# G-CU_2023-06-21_21-38-10.net
KiCad netlist of a schematic drawn in EasyEDA Pro
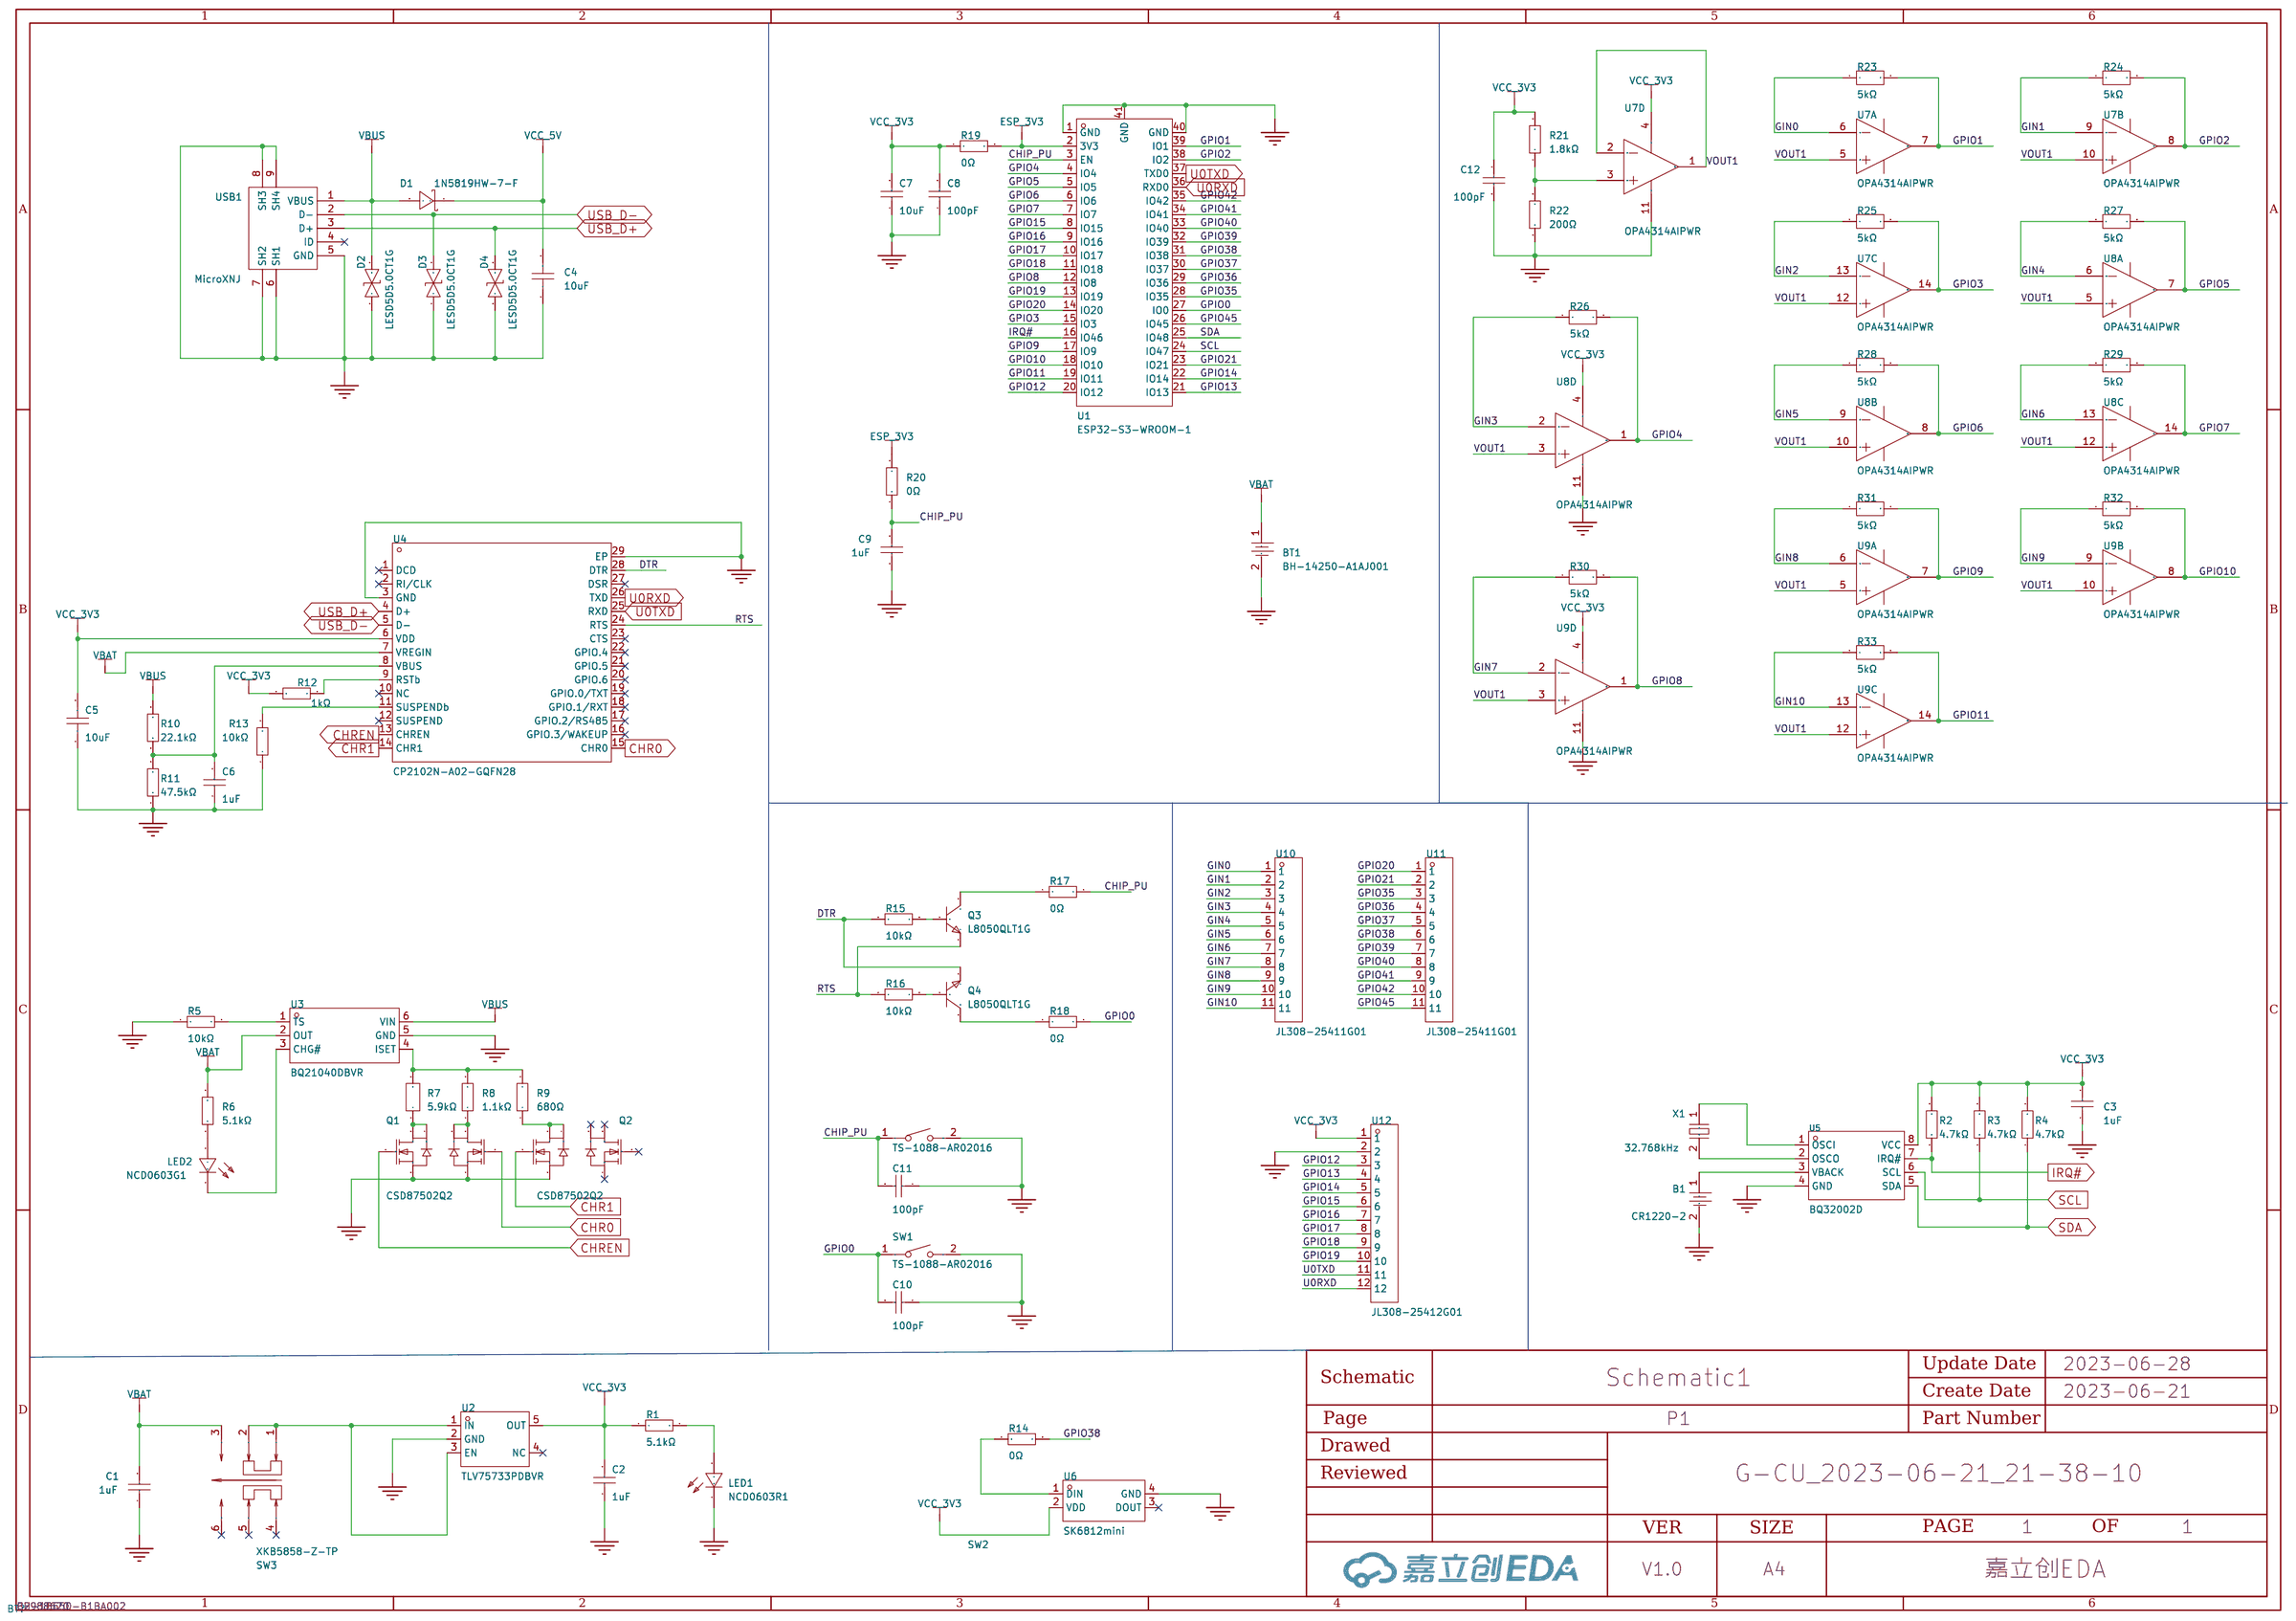
[diagram p0: schematic sheet]

(export (version "E")
  (design (tool "Eeschema 10.0.6"))
  (components
    (comp (ref "B1")
      (value "CR1220-2")
      (footprint "easyedapro:BAT-SMD_CR1220-2")
      (description "连接器类型:电池底座;适用电池规格:CR1220;工作温度范围:-;")
      (fields (field (name "Manufacturer") "Q&J"))
      (libsource (lib "easyedapro") (part "CR1220-2"))
    )
    (comp (ref "BT1")
      (value "BH-14250-A1AJ001")
      (footprint "easyedapro:14250")
      (fields (field (name "Manufacturer") "MYOUNG(美阳)"))
      (libsource (lib "easyedapro") (part "14250"))
    )
    (comp (ref "C1")
      (value "1uF")
      (footprint "easyedapro:C0402")
      (description "容值:1uF;精度:±10%;额定电压:10V;材质(温度系数):X5R;")
      (fields
        (field (name "Manufacturer Part") "CL05A105KP5NNNC")
        (field (name "Manufacturer") "SAMSUNG(三星)")
      )
      (libsource (lib "easyedapro") (part "CL05A105KP5NNNC"))
    )
    (comp (ref "C2")
      (value "1uF")
      (footprint "easyedapro:C0402")
      (description "容值:1uF;精度:±10%;额定电压:10V;材质(温度系数):X5R;")
      (fields
        (field (name "Manufacturer Part") "CL05A105KP5NNNC")
        (field (name "Manufacturer") "SAMSUNG(三星)")
      )
      (libsource (lib "easyedapro") (part "CL05A105KP5NNNC"))
    )
    (comp (ref "C3")
      (value "1uF")
      (footprint "easyedapro:C0402")
      (description "容值:1uF;精度:±10%;额定电压:10V;材质(温度系数):X5R;")
      (fields
        (field (name "Manufacturer Part") "CL05A105KP5NNNC")
        (field (name "Manufacturer") "SAMSUNG(三星)")
      )
      (libsource (lib "easyedapro") (part "CL05A105KP5NNNC"))
    )
    (comp (ref "C4")
      (value "10uF")
      (footprint "easyedapro:C0603")
      (description "容值:10uF;精度:±20%;额定电压:25V;材质(温度系数):X5R;")
      (fields
        (field (name "Manufacturer Part") "CL10A106MA8NRNC")
        (field (name "Manufacturer") "SAMSUNG(三星)")
      )
      (libsource (lib "easyedapro") (part "CL10A106MA8NRNC"))
    )
    (comp (ref "C5")
      (value "10uF")
      (footprint "easyedapro:C0603")
      (description "容值:10uF;精度:±20%;额定电压:25V;材质(温度系数):X5R;")
      (fields
        (field (name "Manufacturer Part") "CL10A106MA8NRNC")
        (field (name "Manufacturer") "SAMSUNG(三星)")
      )
      (libsource (lib "easyedapro") (part "CL10A106MA8NRNC"))
    )
    (comp (ref "C6")
      (value "1uF")
      (footprint "easyedapro:C0603")
      (description "容值:1uF;精度:±10%;额定电压:16V;材质(温度系数):X5R;")
      (fields
        (field (name "Manufacturer Part") "CL10A105KO8NNNC")
        (field (name "Manufacturer") "SAMSUNG(三星)")
      )
      (libsource (lib "easyedapro") (part "CL10A105KO8NNNC"))
    )
    (comp (ref "C7")
      (value "10uF")
      (footprint "easyedapro:C0402")
      (description "容值:10uF;精度:±20%;额定电压:6.3V;材质(温度系数):X5R;")
      (fields
        (field (name "Manufacturer Part") "CL05A106MQ5NUNC")
        (field (name "Manufacturer") "SAMSUNG(三星)")
      )
      (libsource (lib "easyedapro") (part "CL05A106MQ5NUNC"))
    )
    (comp (ref "C8")
      (value "100pF")
      (footprint "easyedapro:C0402")
      (description "容值:100pF;精度:±5%;额定电压:50V;材质(温度系数):C0G;")
      (fields (field (name "Manufacturer Part") "0402CG101J500NT") (field (name "Manufacturer") "FH(风华)"))
      (libsource (lib "easyedapro") (part "0402CG101J500NT"))
    )
    (comp (ref "C9")
      (value "1uF")
      (footprint "easyedapro:C0402")
      (description "容值:1uF;精度:±10%;额定电压:10V;材质(温度系数):X5R;")
      (fields
        (field (name "Manufacturer Part") "CL05A105KP5NNNC")
        (field (name "Manufacturer") "SAMSUNG(三星)")
      )
      (libsource (lib "easyedapro") (part "CL05A105KP5NNNC"))
    )
    (comp (ref "C10")
      (value "100pF")
      (footprint "easyedapro:C0402")
      (description "容值:100pF;精度:±5%;额定电压:50V;材质(温度系数):C0G;")
      (fields (field (name "Manufacturer Part") "0402CG101J500NT") (field (name "Manufacturer") "FH(风华)"))
      (libsource (lib "easyedapro") (part "0402CG101J500NT"))
    )
    (comp (ref "C11")
      (value "100pF")
      (footprint "easyedapro:C0402")
      (description "容值:100pF;精度:±5%;额定电压:50V;材质(温度系数):C0G;")
      (fields (field (name "Manufacturer Part") "0402CG101J500NT") (field (name "Manufacturer") "FH(风华)"))
      (libsource (lib "easyedapro") (part "0402CG101J500NT"))
    )
    (comp (ref "C12")
      (value "100pF")
      (footprint "easyedapro:C0402")
      (description "容值:100pF;精度:±5%;额定电压:50V;材质(温度系数):C0G;")
      (fields (field (name "Manufacturer Part") "0402CG101J500NT") (field (name "Manufacturer") "FH(风华)"))
      (libsource (lib "easyedapro") (part "0402CG101J500NT"))
    )
    (comp (ref "D1")
      (value "1N5819HW-7-F")
      (footprint "easyedapro:SOD-123_L2.7-W1.6-LS3.7-RD")
      (description "直流反向耐压(Vr):40V;平均整流电流(Io):1A;正向压降(Vf):450mV@1A;")
      (fields (field (name "Manufacturer") "DIODES(美台)"))
      (libsource (lib "easyedapro") (part "1N5819HW-7-F"))
    )
    (comp (ref "D2")
      (value "LESD5D5.0CT1G")
      (footprint "easyedapro:SOD-523_L1.2-W0.8-LS1.6-BI")
      (description "极性:双向;反向截止电压(Vrwm):5V;击穿电压(VBR):5.6V;钳位电压(Vc)@Ipp:18.6V;")
      (fields (field (name "Manufacturer") "LRC(乐山无线电)"))
      (libsource (lib "easyedapro") (part "LESD5D5.0CT1G"))
    )
    (comp (ref "D3")
      (value "LESD5D5.0CT1G")
      (footprint "easyedapro:SOD-523_L1.2-W0.8-LS1.6-BI")
      (description "极性:双向;反向截止电压(Vrwm):5V;击穿电压(VBR):5.6V;钳位电压(Vc)@Ipp:18.6V;")
      (fields (field (name "Manufacturer") "LRC(乐山无线电)"))
      (libsource (lib "easyedapro") (part "LESD5D5.0CT1G"))
    )
    (comp (ref "D4")
      (value "LESD5D5.0CT1G")
      (footprint "easyedapro:SOD-523_L1.2-W0.8-LS1.6-BI")
      (description "极性:双向;反向截止电压(Vrwm):5V;击穿电压(VBR):5.6V;钳位电压(Vc)@Ipp:18.6V;")
      (fields (field (name "Manufacturer") "LRC(乐山无线电)"))
      (libsource (lib "easyedapro") (part "LESD5D5.0CT1G"))
    )
    (comp (ref "LED1")
      (value "NCD0603R1")
      (footprint "easyedapro:LED0603-RD_RED")
      (description "发光颜色:红灯;")
      (fields (field (name "Manufacturer") "国星光电"))
      (libsource (lib "easyedapro") (part "FC-DA1608HRK-620D"))
    )
    (comp (ref "LED2")
      (value "NCD0603G1")
      (footprint "easyedapro:LED0603-RD")
      (description "发光颜色:翠绿;")
      (fields (field (name "Manufacturer") "国星光电"))
      (libsource (lib "easyedapro") (part "FC-D1608UGK-520D10"))
    )
    (comp (ref "Q1")
      (value "CSD87502Q2")
      (footprint "easyedapro:DFN-6L_L2.0-W2.0-P0.65-BL-EP")
      (description "类型:2个N沟道;漏源电压(Vdss):30V;连续漏极电流(Id):5A;功率(Pd):2.3W;导通电阻(RDS(on)@Vgs,Id):32.4mΩ@10V,4A;")
      (fields (field (name "Manufacturer") "TI(德州仪器)"))
      (libsource (lib "easyedapro") (part "CSD87502Q2"))
    )
    (comp (ref "Q2")
      (value "CSD87502Q2")
      (footprint "easyedapro:DFN-6L_L2.0-W2.0-P0.65-BL-EP")
      (description "类型:2个N沟道;漏源电压(Vdss):30V;连续漏极电流(Id):5A;功率(Pd):2.3W;导通电阻(RDS(on)@Vgs,Id):32.4mΩ@10V,4A;")
      (fields (field (name "Manufacturer") "TI(德州仪器)"))
      (libsource (lib "easyedapro") (part "CSD87502Q2"))
    )
    (comp (ref "Q3")
      (value "L8050QLT1G")
      (footprint "easyedapro:SOT-23-3_L2.9-W1.3-P1.90-LS2.4-BR")
      (description "晶体管类型:NPN;集射极击穿电压(Vceo):25V;集电极电流(Ic):800mA;功率(Pd):225mW;")
      (fields (field (name "Manufacturer") "LRC(乐山无线电)"))
      (libsource (lib "easyedapro") (part "L8050QLT1G"))
    )
    (comp (ref "Q4")
      (value "L8050QLT1G")
      (footprint "easyedapro:SOT-23-3_L2.9-W1.3-P1.90-LS2.4-BR")
      (description "晶体管类型:NPN;集射极击穿电压(Vceo):25V;集电极电流(Ic):800mA;功率(Pd):225mW;")
      (fields (field (name "Manufacturer") "LRC(乐山无线电)"))
      (libsource (lib "easyedapro") (part "L8050QLT1G"))
    )
    (comp (ref "R1")
      (value "5.1kΩ")
      (footprint "easyedapro:R0402")
      (description "电阻类型:厚膜电阻;阻值:5.1kΩ;精度:±1%;功率:62.5mW;")
      (fields
        (field (name "Manufacturer Part") "0402WGF5101TCE")
        (field (name "Manufacturer") "UNI-ROYAL(厚声)")
      )
      (libsource (lib "easyedapro") (part "0402WGF5101TCE"))
    )
    (comp (ref "R2")
      (value "4.7kΩ")
      (footprint "easyedapro:R0402")
      (description "电阻类型:厚膜电阻;阻值:4.7kΩ;精度:±1%;功率:62.5mW;")
      (fields
        (field (name "Manufacturer Part") "0402WGF4701TCE")
        (field (name "Manufacturer") "UNI-ROYAL(厚声)")
      )
      (libsource (lib "easyedapro") (part "0402WGF4701TCE"))
    )
    (comp (ref "R3")
      (value "4.7kΩ")
      (footprint "easyedapro:R0402")
      (description "电阻类型:厚膜电阻;阻值:4.7kΩ;精度:±1%;功率:62.5mW;")
      (fields
        (field (name "Manufacturer Part") "0402WGF4701TCE")
        (field (name "Manufacturer") "UNI-ROYAL(厚声)")
      )
      (libsource (lib "easyedapro") (part "0402WGF4701TCE"))
    )
    (comp (ref "R4")
      (value "4.7kΩ")
      (footprint "easyedapro:R0402")
      (description "电阻类型:厚膜电阻;阻值:4.7kΩ;精度:±1%;功率:62.5mW;")
      (fields
        (field (name "Manufacturer Part") "0402WGF4701TCE")
        (field (name "Manufacturer") "UNI-ROYAL(厚声)")
      )
      (libsource (lib "easyedapro") (part "0402WGF4701TCE"))
    )
    (comp (ref "R5")
      (value "10kΩ")
      (footprint "easyedapro:R0402")
      (description "电阻类型:厚膜电阻;阻值:10kΩ;精度:±1%;功率:62.5mW;")
      (fields
        (field (name "Manufacturer Part") "0402WGF1002TCE")
        (field (name "Manufacturer") "UNI-ROYAL(厚声)")
      )
      (libsource (lib "easyedapro") (part "0402WGF1002TCE"))
    )
    (comp (ref "R6")
      (value "5.1kΩ")
      (footprint "easyedapro:R0402")
      (description "电阻类型:厚膜电阻;阻值:5.1kΩ;精度:±1%;功率:62.5mW;")
      (fields
        (field (name "Manufacturer Part") "0402WGF5101TCE")
        (field (name "Manufacturer") "UNI-ROYAL(厚声)")
      )
      (libsource (lib "easyedapro") (part "0402WGF5101TCE"))
    )
    (comp (ref "R7")
      (value "5.9kΩ")
      (footprint "easyedapro:R0402")
      (description "电阻类型:厚膜电阻;阻值:5.9kΩ;精度:±1%;功率:62.5mW;温度系数:±100ppm/°C;最大工作电压:50V;工作温度范围:-55°C~+125°C;")
      (fields (field (name "Manufacturer Part") "RC0402FR-075K9L") (field (name "Manufacturer") "YAGEO(国巨)"))
      (libsource (lib "easyedapro") (part "RC0402FR-075K9L"))
    )
    (comp (ref "R8")
      (value "1.1kΩ")
      (footprint "easyedapro:R0402")
      (description "电阻类型:厚膜电阻;阻值:1.1kΩ;精度:±1%;功率:62.5mW;")
      (fields
        (field (name "Manufacturer Part") "0402WGF1101TCE")
        (field (name "Manufacturer") "UNI-ROYAL(厚声)")
      )
      (libsource (lib "easyedapro") (part "0402WGF1101TCE"))
    )
    (comp (ref "R9")
      (value "680Ω")
      (footprint "easyedapro:R0402")
      (description "电阻类型:厚膜电阻;阻值:680Ω;精度:±1%;功率:62.5mW;")
      (fields
        (field (name "Manufacturer Part") "0402WGF6800TCE")
        (field (name "Manufacturer") "UNI-ROYAL(厚声)")
      )
      (libsource (lib "easyedapro") (part "0402WGF6800TCE"))
    )
    (comp (ref "R10")
      (value "22.1kΩ")
      (footprint "easyedapro:R0402")
      (description "电阻类型:厚膜电阻;阻值:22.1kΩ;精度:±1%;功率:62.5mW;")
      (fields
        (field (name "Manufacturer Part") "0402WGF2212TCE")
        (field (name "Manufacturer") "UNI-ROYAL(厚声)")
      )
      (libsource (lib "easyedapro") (part "0402WGF2212TCE"))
    )
    (comp (ref "R11")
      (value "47.5kΩ")
      (footprint "easyedapro:R0402")
      (description "电阻类型:厚膜电阻;阻值:47.5kΩ;精度:±1%;功率:62.5mW;")
      (fields
        (field (name "Manufacturer Part") "0402WGF4752TCE")
        (field (name "Manufacturer") "UNI-ROYAL(厚声)")
      )
      (libsource (lib "easyedapro") (part "0402WGF4752TCE"))
    )
    (comp (ref "R12")
      (value "1kΩ")
      (footprint "easyedapro:R0402")
      (description "电阻类型:厚膜电阻;阻值:1kΩ;精度:±1%;功率:62.5mW;")
      (fields
        (field (name "Manufacturer Part") "0402WGF1001TCE")
        (field (name "Manufacturer") "UNI-ROYAL(厚声)")
      )
      (libsource (lib "easyedapro") (part "0402WGF1001TCE"))
    )
    (comp (ref "R13")
      (value "10kΩ")
      (footprint "easyedapro:R0402")
      (description "电阻类型:厚膜电阻;阻值:10kΩ;精度:±1%;功率:62.5mW;")
      (fields
        (field (name "Manufacturer Part") "0402WGF1002TCE")
        (field (name "Manufacturer") "UNI-ROYAL(厚声)")
      )
      (libsource (lib "easyedapro") (part "0402WGF1002TCE"))
    )
    (comp (ref "R14")
      (value "0Ω")
      (footprint "easyedapro:R0402")
      (description "电阻类型:厚膜电阻;阻值:0Ω;精度:±5%;功率:62.5mW;")
      (fields
        (field (name "Manufacturer Part") "0402WGJ0000TCE")
        (field (name "Manufacturer") "UNI-ROYAL(厚声)")
      )
      (libsource (lib "easyedapro") (part "0402WGJ0000TCE"))
    )
    (comp (ref "R15")
      (value "10kΩ")
      (footprint "easyedapro:R0402")
      (description "电阻类型:厚膜电阻;阻值:10kΩ;精度:±1%;功率:62.5mW;")
      (fields
        (field (name "Manufacturer Part") "0402WGF1002TCE")
        (field (name "Manufacturer") "UNI-ROYAL(厚声)")
      )
      (libsource (lib "easyedapro") (part "0402WGF1002TCE"))
    )
    (comp (ref "R16")
      (value "10kΩ")
      (footprint "easyedapro:R0402")
      (description "电阻类型:厚膜电阻;阻值:10kΩ;精度:±1%;功率:62.5mW;")
      (fields
        (field (name "Manufacturer Part") "0402WGF1002TCE")
        (field (name "Manufacturer") "UNI-ROYAL(厚声)")
      )
      (libsource (lib "easyedapro") (part "0402WGF1002TCE"))
    )
    (comp (ref "R17")
      (value "0Ω")
      (footprint "easyedapro:R0402")
      (description "电阻类型:厚膜电阻;阻值:0Ω;精度:±5%;功率:62.5mW;")
      (fields
        (field (name "Manufacturer Part") "0402WGJ0000TCE")
        (field (name "Manufacturer") "UNI-ROYAL(厚声)")
      )
      (libsource (lib "easyedapro") (part "0402WGJ0000TCE"))
    )
    (comp (ref "R18")
      (value "0Ω")
      (footprint "easyedapro:R0402")
      (description "电阻类型:厚膜电阻;阻值:0Ω;精度:±5%;功率:62.5mW;")
      (fields
        (field (name "Manufacturer Part") "0402WGJ0000TCE")
        (field (name "Manufacturer") "UNI-ROYAL(厚声)")
      )
      (libsource (lib "easyedapro") (part "0402WGJ0000TCE"))
    )
    (comp (ref "R19")
      (value "0Ω")
      (footprint "easyedapro:R0402")
      (description "电阻类型:厚膜电阻;阻值:0Ω;精度:±5%;功率:62.5mW;")
      (fields
        (field (name "Manufacturer Part") "0402WGJ0000TCE")
        (field (name "Manufacturer") "UNI-ROYAL(厚声)")
      )
      (libsource (lib "easyedapro") (part "0402WGJ0000TCE"))
    )
    (comp (ref "R20")
      (value "0Ω")
      (footprint "easyedapro:R0402")
      (description "电阻类型:厚膜电阻;阻值:0Ω;精度:±5%;功率:62.5mW;")
      (fields
        (field (name "Manufacturer Part") "0402WGJ0000TCE")
        (field (name "Manufacturer") "UNI-ROYAL(厚声)")
      )
      (libsource (lib "easyedapro") (part "0402WGJ0000TCE"))
    )
    (comp (ref "R21")
      (value "1.8kΩ")
      (footprint "easyedapro:R0402")
      (description "电阻类型:厚膜电阻;阻值:1.8kΩ;精度:±1%;功率:62.5mW;")
      (fields
        (field (name "Manufacturer Part") "0402WGF1801TCE")
        (field (name "Manufacturer") "UNI-ROYAL(厚声)")
      )
      (libsource (lib "easyedapro") (part "0402WGF1801TCE"))
    )
    (comp (ref "R22")
      (value "200Ω")
      (footprint "easyedapro:R0402")
      (description "电阻类型:厚膜电阻;阻值:200Ω;精度:±1%;功率:62.5mW;")
      (fields
        (field (name "Manufacturer Part") "0402WGF2000TCE")
        (field (name "Manufacturer") "UNI-ROYAL(厚声)")
      )
      (libsource (lib "easyedapro") (part "0402WGF2000TCE"))
    )
    (comp (ref "R23")
      (value "5kΩ")
      (footprint "easyedapro:R0603")
      (description "电阻类型:薄膜电阻;阻值:5kΩ;精度:±0.1%;功率:100mW;")
      (fields (field (name "Manufacturer Part") "AR03BTCX5001") (field (name "Manufacturer") "Viking(光颉)"))
      (libsource (lib "easyedapro") (part "AR03BTCX5001"))
    )
    (comp (ref "R24")
      (value "5kΩ")
      (footprint "easyedapro:R0603")
      (description "电阻类型:薄膜电阻;阻值:5kΩ;精度:±0.1%;功率:100mW;")
      (fields (field (name "Manufacturer Part") "AR03BTCX5001") (field (name "Manufacturer") "Viking(光颉)"))
      (libsource (lib "easyedapro") (part "AR03BTCX5001"))
    )
    (comp (ref "R25")
      (value "5kΩ")
      (footprint "easyedapro:R0603")
      (description "电阻类型:薄膜电阻;阻值:5kΩ;精度:±0.1%;功率:100mW;")
      (fields (field (name "Manufacturer Part") "AR03BTCX5001") (field (name "Manufacturer") "Viking(光颉)"))
      (libsource (lib "easyedapro") (part "AR03BTCX5001"))
    )
    (comp (ref "R26")
      (value "5kΩ")
      (footprint "easyedapro:R0603")
      (description "电阻类型:薄膜电阻;阻值:5kΩ;精度:±0.1%;功率:100mW;")
      (fields (field (name "Manufacturer Part") "AR03BTCX5001") (field (name "Manufacturer") "Viking(光颉)"))
      (libsource (lib "easyedapro") (part "AR03BTCX5001"))
    )
    (comp (ref "R27")
      (value "5kΩ")
      (footprint "easyedapro:R0603")
      (description "电阻类型:薄膜电阻;阻值:5kΩ;精度:±0.1%;功率:100mW;")
      (fields (field (name "Manufacturer Part") "AR03BTCX5001") (field (name "Manufacturer") "Viking(光颉)"))
      (libsource (lib "easyedapro") (part "AR03BTCX5001"))
    )
    (comp (ref "R28")
      (value "5kΩ")
      (footprint "easyedapro:R0603")
      (description "电阻类型:薄膜电阻;阻值:5kΩ;精度:±0.1%;功率:100mW;")
      (fields (field (name "Manufacturer Part") "AR03BTCX5001") (field (name "Manufacturer") "Viking(光颉)"))
      (libsource (lib "easyedapro") (part "AR03BTCX5001"))
    )
    (comp (ref "R29")
      (value "5kΩ")
      (footprint "easyedapro:R0603")
      (description "电阻类型:薄膜电阻;阻值:5kΩ;精度:±0.1%;功率:100mW;")
      (fields (field (name "Manufacturer Part") "AR03BTCX5001") (field (name "Manufacturer") "Viking(光颉)"))
      (libsource (lib "easyedapro") (part "AR03BTCX5001"))
    )
    (comp (ref "R30")
      (value "5kΩ")
      (footprint "easyedapro:R0603")
      (description "电阻类型:薄膜电阻;阻值:5kΩ;精度:±0.1%;功率:100mW;")
      (fields (field (name "Manufacturer Part") "AR03BTCX5001") (field (name "Manufacturer") "Viking(光颉)"))
      (libsource (lib "easyedapro") (part "AR03BTCX5001"))
    )
    (comp (ref "R31")
      (value "5kΩ")
      (footprint "easyedapro:R0603")
      (description "电阻类型:薄膜电阻;阻值:5kΩ;精度:±0.1%;功率:100mW;")
      (fields (field (name "Manufacturer Part") "AR03BTCX5001") (field (name "Manufacturer") "Viking(光颉)"))
      (libsource (lib "easyedapro") (part "AR03BTCX5001"))
    )
    (comp (ref "R32")
      (value "5kΩ")
      (footprint "easyedapro:R0603")
      (description "电阻类型:薄膜电阻;阻值:5kΩ;精度:±0.1%;功率:100mW;")
      (fields (field (name "Manufacturer Part") "AR03BTCX5001") (field (name "Manufacturer") "Viking(光颉)"))
      (libsource (lib "easyedapro") (part "AR03BTCX5001"))
    )
    (comp (ref "R33")
      (value "5kΩ")
      (footprint "easyedapro:R0603")
      (description "电阻类型:薄膜电阻;阻值:5kΩ;精度:±0.1%;功率:100mW;")
      (fields (field (name "Manufacturer Part") "AR03BTCX5001") (field (name "Manufacturer") "Viking(光颉)"))
      (libsource (lib "easyedapro") (part "AR03BTCX5001"))
    )
    (comp (ref "SW1")
      (value "TS-1088-AR02016")
      (footprint "easyedapro:SW-SMD_L3.9-W3.0-P4.45")
      (description "触点电流:50mA;额定电压(DC):12V;绝缘电阻:100MΩ;电路结构:单刀单掷;安装方式:立贴;作用力:160gf@±50gf;机械寿命:10万次;带支架:否;")
      (fields (field (name "Manufacturer") "XUNPU(讯普)"))
      (libsource (lib "easyedapro") (part "TS-1088-AR02016"))
    )
    (comp (ref "SW2")
      (value "TS-1088-AR02016")
      (footprint "easyedapro:SW-SMD_L3.9-W3.0-P4.45")
      (description "触点电流:50mA;额定电压(DC):12V;绝缘电阻:100MΩ;电路结构:单刀单掷;安装方式:立贴;作用力:160gf@±50gf;机械寿命:10万次;带支架:否;")
      (fields (field (name "Manufacturer") "XUNPU(讯普)"))
      (libsource (lib "easyedapro") (part "TS-1088-AR02016"))
    )
    (comp (ref "SW3")
      (value "XKB5858-Z-TP")
      (footprint "easyedapro:SW-SMD_6P-L5.8-W5.8-P2.00-LS8.5-1")
      (fields (field (name "Manufacturer") "XKB Connectivity(中国星坤)"))
      (libsource (lib "easyedapro") (part "XKB5858-Z-TP_C840833"))
    )
    (comp (ref "U1")
      (value "ESP32-S3-WROOM-1")
      (footprint "easyedapro:WIRELM-SMD_ESP32-S3-WROOM-1")
      (fields (field (name "Manufacturer") "ESPRESSIF(乐鑫)"))
      (libsource (lib "easyedapro") (part "ESP32-S3-WROOM-1"))
    )
    (comp (ref "U2")
      (value "TLV75733PDBVR")
      (footprint "easyedapro:SOT-23-5_L2.9-W1.6-P0.95-LS2.8-BL")
      (description "输出类型:固定;输出极性:正;输出通道数:1;最大输入电压:5.5V;输出电压:3.3V;压差:475mV@(1A);输出电流:1A;电源纹波抑制比(PSRR):52dB;")
      (fields (field (name "Manufacturer") "TI(德州仪器)"))
      (libsource (lib "easyedapro") (part "TLV75733PDBVR"))
    )
    (comp (ref "U3")
      (value "BQ21040DBVR")
      (footprint "easyedapro:SOT-23-6_L2.9-W1.6-P0.95-LS2.8-BR")
      (description "电池类型:锂离子/聚合物;电池节数:1;最大充电电流:800mA;电源电压:6.45V;")
      (fields (field (name "Manufacturer") "TI(德州仪器)"))
      (libsource (lib "easyedapro") (part "BQ21040DBVR"))
    )
    (comp (ref "U4")
      (value "CP2102N-A02-GQFN28")
      (footprint "easyedapro:QFN-28_L5.0-W5.0-P0.50-TL-EP3.3")
      (fields (field (name "Manufacturer") "SILICON LABS(芯科)"))
      (libsource (lib "easyedapro") (part "CP2102N-A02-GQFN28"))
    )
    (comp (ref "U5")
      (value "BQ32002D")
      (footprint "easyedapro:SOIC-8_L4.9-W3.9-P1.27-LS6.0-BL")
      (description "实时时钟 (RTC) 8-SOIC -40 to 85")
      (fields (field (name "Manufacturer") "TI(德州仪器)"))
      (libsource (lib "easyedapro") (part "BQ32002D"))
    )
    (comp (ref "U6")
      (value "SK6812mini")
      (footprint "easyedapro:LED-SMD_4P-L3.7-W3.5-P1.75-BR-SK6812MINI")
      (fields (field (name "Manufacturer") "欧思科光电"))
      (libsource (lib "easyedapro") (part "SK6812MINI"))
    )
    (comp (ref "U7")
      (value "OPA4314AIPWR")
      (footprint "easyedapro:TSSOP-14_L5.0-W4.4-P0.65-LS6.4-BL")
      (description "OPA4314 四路、3MHz、低功耗、低噪声、RRI/O、1.8V CMOS 运算放大器")
      (fields (field (name "Manufacturer") "TI(德州仪器)"))
      (libsource (lib "easyedapro") (part "OPA4314AIPWR"))
    )
    (comp (ref "U8")
      (value "OPA4314AIPWR")
      (footprint "easyedapro:TSSOP-14_L5.0-W4.4-P0.65-LS6.4-BL")
      (description "OPA4314 四路、3MHz、低功耗、低噪声、RRI/O、1.8V CMOS 运算放大器")
      (fields (field (name "Manufacturer") "TI(德州仪器)"))
      (libsource (lib "easyedapro") (part "OPA4314AIPWR"))
    )
    (comp (ref "U9")
      (value "OPA4314AIPWR")
      (footprint "easyedapro:TSSOP-14_L5.0-W4.4-P0.65-LS6.4-BL")
      (description "OPA4314 四路、3MHz、低功耗、低噪声、RRI/O、1.8V CMOS 运算放大器")
      (fields (field (name "Manufacturer") "TI(德州仪器)"))
      (libsource (lib "easyedapro") (part "OPA4314AIPWR"))
    )
    (comp (ref "U10")
      (value "JL308-25411G01")
      (footprint "easyedapro:CONN-TH_11P-P2.54_JILN_JL308-25411G01")
      (fields (field (name "Manufacturer") "JILN(锦凌)"))
      (libsource (lib "easyedapro") (part "JL308-25411G01"))
    )
    (comp (ref "U11")
      (value "JL308-25411G01")
      (footprint "easyedapro:CONN-TH_11P-P2.54_JILN_JL308-25411G01")
      (fields (field (name "Manufacturer") "JILN(锦凌)"))
      (libsource (lib "easyedapro") (part "JL308-25411G01"))
    )
    (comp (ref "U12")
      (value "JL308-25412G01")
      (footprint "easyedapro:CONN-TH_12P-P2.54_JILN_JL308-25412G01")
      (fields (field (name "Manufacturer") "JILN(锦凌)"))
      (libsource (lib "easyedapro") (part "JL308-25412G01"))
    )
    (comp (ref "USB1")
      (value "MicroXNJ")
      (footprint "easyedapro:MICRO-USB-SMD_MICROXNJ")
      (description "连接器类型:Micro-B;标准:USB 2.0;公母:母座;触点数量:5;端口数量:1;安装方式:卧贴;额定电流 - 电源:1A;工作温度范围:-20°C~+85°C;")
      (fields (field (name "Manufacturer") "SHOU HAN(首韩)"))
      (libsource (lib "easyedapro") (part "MICROXNJ"))
    )
    (comp (ref "X1")
      (value "32.768kHz")
      (footprint "easyedapro:CRYSTAL-SMD_L3.2-W1.5")
      (description "频率:32.768kHz;频率公差:±10ppm;负载电容:12.5pF;")
      (fields (field (name "Manufacturer Part") "Q13FC13500005") (field (name "Manufacturer") "EPSON(爱普生)"))
      (libsource (lib "easyedapro") (part "Q13FC13500005"))
    )
  )
  (nets
    (net (code "1") (name "/CHIP_PU") (class "Default")
      (node (ref "C11") (pin "2") (pinfunction "2_2") (pintype "input"))
      (node (ref "C9") (pin "2") (pinfunction "2_2") (pintype "input"))
      (node (ref "R17") (pin "2") (pinfunction "2_2") (pintype "input"))
      (node (ref "R20") (pin "1") (pinfunction "1_1") (pintype "input"))
      (node (ref "SW2") (pin "1") (pinfunction "1_1") (pintype "input"))
      (node (ref "U1") (pin "3") (pinfunction "EN_3") (pintype "input"))
    )
    (net (code "2") (name "/DTR") (class "Default")
      (node (ref "Q4") (pin "2") (pinfunction "E_2") (pintype "input"))
      (node (ref "R15") (pin "1") (pinfunction "1_1") (pintype "input"))
      (node (ref "U4") (pin "28") (pinfunction "DTR_28") (pintype "input"))
    )
    (net (code "3") (name "/GIN0") (class "Default")
      (node (ref "R23") (pin "1") (pinfunction "1_1") (pintype "input"))
      (node (ref "U10") (pin "1") (pinfunction "1_1") (pintype "input"))
      (node (ref "U7") (pin "6") (pinfunction "IN_B-_6") (pintype "input"))
    )
    (net (code "4") (name "/GIN1") (class "Default")
      (node (ref "R24") (pin "1") (pinfunction "1_1") (pintype "input"))
      (node (ref "U10") (pin "2") (pinfunction "2_2") (pintype "input"))
      (node (ref "U7") (pin "9") (pinfunction "IN_C-_9") (pintype "input"))
    )
    (net (code "5") (name "/GIN2") (class "Default")
      (node (ref "R25") (pin "1") (pinfunction "1_1") (pintype "input"))
      (node (ref "U10") (pin "3") (pinfunction "3_3") (pintype "input"))
      (node (ref "U7") (pin "13") (pinfunction "IN_D-_13") (pintype "input"))
    )
    (net (code "6") (name "/GIN3") (class "Default")
      (node (ref "R26") (pin "1") (pinfunction "1_1") (pintype "input"))
      (node (ref "U10") (pin "4") (pinfunction "4_4") (pintype "input"))
      (node (ref "U8") (pin "2") (pinfunction "IN_A-_2") (pintype "input"))
    )
    (net (code "7") (name "/GIN4") (class "Default")
      (node (ref "R27") (pin "1") (pinfunction "1_1") (pintype "input"))
      (node (ref "U10") (pin "5") (pinfunction "5_5") (pintype "input"))
      (node (ref "U8") (pin "6") (pinfunction "IN_B-_6") (pintype "input"))
    )
    (net (code "8") (name "/GIN5") (class "Default")
      (node (ref "R28") (pin "1") (pinfunction "1_1") (pintype "input"))
      (node (ref "U10") (pin "6") (pinfunction "6_6") (pintype "input"))
      (node (ref "U8") (pin "9") (pinfunction "IN_C-_9") (pintype "input"))
    )
    (net (code "9") (name "/GIN6") (class "Default")
      (node (ref "R29") (pin "1") (pinfunction "1_1") (pintype "input"))
      (node (ref "U10") (pin "7") (pinfunction "7_7") (pintype "input"))
      (node (ref "U8") (pin "13") (pinfunction "IN_D-_13") (pintype "input"))
    )
    (net (code "10") (name "/GIN7") (class "Default")
      (node (ref "R30") (pin "1") (pinfunction "1_1") (pintype "input"))
      (node (ref "U10") (pin "8") (pinfunction "8_8") (pintype "input"))
      (node (ref "U9") (pin "2") (pinfunction "IN_A-_2") (pintype "input"))
    )
    (net (code "11") (name "/GIN8") (class "Default")
      (node (ref "R31") (pin "1") (pinfunction "1_1") (pintype "input"))
      (node (ref "U10") (pin "9") (pinfunction "9_9") (pintype "input"))
      (node (ref "U9") (pin "6") (pinfunction "IN_B-_6") (pintype "input"))
    )
    (net (code "12") (name "/GIN9") (class "Default")
      (node (ref "R32") (pin "1") (pinfunction "1_1") (pintype "input"))
      (node (ref "U10") (pin "10") (pinfunction "10_10") (pintype "input"))
      (node (ref "U9") (pin "9") (pinfunction "IN_C-_9") (pintype "input"))
    )
    (net (code "13") (name "/GIN10") (class "Default")
      (node (ref "R33") (pin "1") (pinfunction "1_1") (pintype "input"))
      (node (ref "U10") (pin "11") (pinfunction "11_11") (pintype "input"))
      (node (ref "U9") (pin "13") (pinfunction "IN_D-_13") (pintype "input"))
    )
    (net (code "14") (name "/GPIO0") (class "Default")
      (node (ref "C10") (pin "2") (pinfunction "2_2") (pintype "input"))
      (node (ref "R18") (pin "2") (pinfunction "2_2") (pintype "input"))
      (node (ref "SW1") (pin "1") (pinfunction "1_1") (pintype "input"))
      (node (ref "U1") (pin "27") (pinfunction "IO0_27") (pintype "input"))
    )
    (net (code "15") (name "/GPIO1") (class "Default")
      (node (ref "R23") (pin "2") (pinfunction "2_2") (pintype "input"))
      (node (ref "U1") (pin "39") (pinfunction "IO1_39") (pintype "input"))
      (node (ref "U7") (pin "7") (pinfunction "OUT_B_7") (pintype "output"))
    )
    (net (code "16") (name "/GPIO2") (class "Default")
      (node (ref "R24") (pin "2") (pinfunction "2_2") (pintype "input"))
      (node (ref "U1") (pin "38") (pinfunction "IO2_38") (pintype "input"))
      (node (ref "U7") (pin "8") (pinfunction "OUT_C_8") (pintype "output"))
    )
    (net (code "17") (name "/GPIO3") (class "Default")
      (node (ref "R25") (pin "2") (pinfunction "2_2") (pintype "input"))
      (node (ref "U1") (pin "15") (pinfunction "IO3_15") (pintype "input"))
      (node (ref "U7") (pin "14") (pinfunction "OUT_D_14") (pintype "output"))
    )
    (net (code "18") (name "/GPIO4") (class "Default")
      (node (ref "R26") (pin "2") (pinfunction "2_2") (pintype "input"))
      (node (ref "U1") (pin "4") (pinfunction "IO4_4") (pintype "input"))
      (node (ref "U8") (pin "1") (pinfunction "OUT_A_1") (pintype "output"))
    )
    (net (code "19") (name "/GPIO5") (class "Default")
      (node (ref "R27") (pin "2") (pinfunction "2_2") (pintype "input"))
      (node (ref "U1") (pin "5") (pinfunction "IO5_5") (pintype "input"))
      (node (ref "U8") (pin "7") (pinfunction "OUT_B_7") (pintype "output"))
    )
    (net (code "20") (name "/GPIO6") (class "Default")
      (node (ref "R28") (pin "2") (pinfunction "2_2") (pintype "input"))
      (node (ref "U1") (pin "6") (pinfunction "IO6_6") (pintype "input"))
      (node (ref "U8") (pin "8") (pinfunction "OUT_C_8") (pintype "output"))
    )
    (net (code "21") (name "/GPIO7") (class "Default")
      (node (ref "R29") (pin "2") (pinfunction "2_2") (pintype "input"))
      (node (ref "U1") (pin "7") (pinfunction "IO7_7") (pintype "input"))
      (node (ref "U8") (pin "14") (pinfunction "OUT_D_14") (pintype "output"))
    )
    (net (code "22") (name "/GPIO8") (class "Default")
      (node (ref "R30") (pin "2") (pinfunction "2_2") (pintype "input"))
      (node (ref "U1") (pin "12") (pinfunction "IO8_12") (pintype "input"))
      (node (ref "U9") (pin "1") (pinfunction "OUT_A_1") (pintype "output"))
    )
    (net (code "23") (name "/GPIO9") (class "Default")
      (node (ref "R31") (pin "2") (pinfunction "2_2") (pintype "input"))
      (node (ref "U1") (pin "17") (pinfunction "IO9_17") (pintype "input"))
      (node (ref "U9") (pin "7") (pinfunction "OUT_B_7") (pintype "output"))
    )
    (net (code "24") (name "/GPIO10") (class "Default")
      (node (ref "R32") (pin "2") (pinfunction "2_2") (pintype "input"))
      (node (ref "U1") (pin "18") (pinfunction "IO10_18") (pintype "input"))
      (node (ref "U9") (pin "8") (pinfunction "OUT_C_8") (pintype "output"))
    )
    (net (code "25") (name "/GPIO11") (class "Default")
      (node (ref "R33") (pin "2") (pinfunction "2_2") (pintype "input"))
      (node (ref "U1") (pin "19") (pinfunction "IO11_19") (pintype "input"))
      (node (ref "U9") (pin "14") (pinfunction "OUT_D_14") (pintype "output"))
    )
    (net (code "26") (name "/GPIO12") (class "Default")
      (node (ref "U1") (pin "20") (pinfunction "IO12_20") (pintype "input"))
      (node (ref "U12") (pin "3") (pinfunction "3_3") (pintype "input"))
    )
    (net (code "27") (name "/GPIO13") (class "Default")
      (node (ref "U1") (pin "21") (pinfunction "IO13_21") (pintype "input"))
      (node (ref "U12") (pin "4") (pinfunction "4_4") (pintype "input"))
    )
    (net (code "28") (name "/GPIO14") (class "Default")
      (node (ref "U1") (pin "22") (pinfunction "IO14_22") (pintype "input"))
      (node (ref "U12") (pin "5") (pinfunction "5_5") (pintype "input"))
    )
    (net (code "29") (name "/GPIO15") (class "Default")
      (node (ref "U1") (pin "8") (pinfunction "IO15_8") (pintype "input"))
      (node (ref "U12") (pin "6") (pinfunction "6_6") (pintype "input"))
    )
    (net (code "30") (name "/GPIO16") (class "Default")
      (node (ref "U1") (pin "9") (pinfunction "IO16_9") (pintype "input"))
      (node (ref "U12") (pin "7") (pinfunction "7_7") (pintype "input"))
    )
    (net (code "31") (name "/GPIO17") (class "Default")
      (node (ref "U1") (pin "10") (pinfunction "IO17_10") (pintype "input"))
      (node (ref "U12") (pin "8") (pinfunction "8_8") (pintype "input"))
    )
    (net (code "32") (name "/GPIO18") (class "Default")
      (node (ref "U1") (pin "11") (pinfunction "IO18_11") (pintype "input"))
      (node (ref "U12") (pin "9") (pinfunction "9_9") (pintype "input"))
    )
    (net (code "33") (name "/GPIO19") (class "Default")
      (node (ref "U1") (pin "13") (pinfunction "IO19_13") (pintype "input"))
      (node (ref "U12") (pin "10") (pinfunction "10_10") (pintype "input"))
    )
    (net (code "34") (name "/GPIO20") (class "Default")
      (node (ref "U1") (pin "14") (pinfunction "IO20_14") (pintype "input"))
      (node (ref "U11") (pin "1") (pinfunction "1_1") (pintype "input"))
    )
    (net (code "35") (name "/GPIO21") (class "Default")
      (node (ref "U1") (pin "23") (pinfunction "IO21_23") (pintype "input"))
      (node (ref "U11") (pin "2") (pinfunction "2_2") (pintype "input"))
    )
    (net (code "36") (name "/GPIO35") (class "Default")
      (node (ref "U1") (pin "28") (pinfunction "IO35_28") (pintype "input"))
      (node (ref "U11") (pin "3") (pinfunction "3_3") (pintype "input"))
    )
    (net (code "37") (name "/GPIO36") (class "Default")
      (node (ref "U1") (pin "29") (pinfunction "IO36_29") (pintype "input"))
      (node (ref "U11") (pin "4") (pinfunction "4_4") (pintype "input"))
    )
    (net (code "38") (name "/GPIO37") (class "Default")
      (node (ref "U1") (pin "30") (pinfunction "IO37_30") (pintype "input"))
      (node (ref "U11") (pin "5") (pinfunction "5_5") (pintype "input"))
    )
    (net (code "39") (name "/GPIO38") (class "Default")
      (node (ref "R14") (pin "2") (pinfunction "2_2") (pintype "input"))
      (node (ref "U1") (pin "31") (pinfunction "IO38_31") (pintype "input"))
      (node (ref "U11") (pin "6") (pinfunction "6_6") (pintype "input"))
    )
    (net (code "40") (name "/GPIO39") (class "Default")
      (node (ref "U1") (pin "32") (pinfunction "IO39_32") (pintype "input"))
      (node (ref "U11") (pin "7") (pinfunction "7_7") (pintype "input"))
    )
    (net (code "41") (name "/GPIO40") (class "Default")
      (node (ref "U1") (pin "33") (pinfunction "IO40_33") (pintype "input"))
      (node (ref "U11") (pin "8") (pinfunction "8_8") (pintype "input"))
    )
    (net (code "42") (name "/GPIO41") (class "Default")
      (node (ref "U1") (pin "34") (pinfunction "IO41_34") (pintype "input"))
      (node (ref "U11") (pin "9") (pinfunction "9_9") (pintype "input"))
    )
    (net (code "43") (name "/GPIO42") (class "Default")
      (node (ref "U1") (pin "35") (pinfunction "IO42_35") (pintype "input"))
      (node (ref "U11") (pin "10") (pinfunction "10_10") (pintype "input"))
    )
    (net (code "44") (name "/GPIO45") (class "Default")
      (node (ref "U1") (pin "26") (pinfunction "IO45_26") (pintype "input"))
      (node (ref "U11") (pin "11") (pinfunction "11_11") (pintype "input"))
    )
    (net (code "45") (name "/RTS") (class "Default")
      (node (ref "Q3") (pin "2") (pinfunction "E_2") (pintype "input"))
      (node (ref "R16") (pin "1") (pinfunction "1_1") (pintype "input"))
      (node (ref "U4") (pin "24") (pinfunction "RTS_24") (pintype "input"))
    )
    (net (code "46") (name "/VOUT1") (class "Default")
      (node (ref "U7") (pin "1") (pinfunction "OUT_A_1") (pintype "output"))
      (node (ref "U7") (pin "10") (pinfunction "IN_C+_10") (pintype "input"))
      (node (ref "U7") (pin "12") (pinfunction "IN_D+_12") (pintype "input"))
      (node (ref "U7") (pin "2") (pinfunction "IN_A-_2") (pintype "input"))
      (node (ref "U7") (pin "5") (pinfunction "IN_B+_5") (pintype "input"))
      (node (ref "U8") (pin "10") (pinfunction "IN_C+_10") (pintype "input"))
      (node (ref "U8") (pin "12") (pinfunction "IN_D+_12") (pintype "input"))
      (node (ref "U8") (pin "3") (pinfunction "IN_A+_3") (pintype "input"))
      (node (ref "U8") (pin "5") (pinfunction "IN_B+_5") (pintype "input"))
      (node (ref "U9") (pin "10") (pinfunction "IN_C+_10") (pintype "input"))
      (node (ref "U9") (pin "12") (pinfunction "IN_D+_12") (pintype "input"))
      (node (ref "U9") (pin "3") (pinfunction "IN_A+_3") (pintype "input"))
      (node (ref "U9") (pin "5") (pinfunction "IN_B+_5") (pintype "input"))
    )
    (net (code "47") (name "CHR0") (class "Default")
      (node (ref "Q1") (pin "5") (pinfunction "G_5") (pintype "input"))
      (node (ref "U4") (pin "15") (pinfunction "CHR0_15") (pintype "input"))
    )
    (net (code "48") (name "CHR1") (class "Default")
      (node (ref "Q2") (pin "2") (pinfunction "G_2") (pintype "input"))
      (node (ref "U4") (pin "14") (pinfunction "CHR1_14") (pintype "input"))
    )
    (net (code "49") (name "CHREN") (class "Default")
      (node (ref "Q1") (pin "2") (pinfunction "G_2") (pintype "input"))
      (node (ref "U4") (pin "13") (pinfunction "CHREN_13") (pintype "input"))
    )
    (net (code "50") (name "ESP_3V3") (class "Default")
      (node (ref "R19") (pin "2") (pinfunction "2_2") (pintype "input"))
      (node (ref "R20") (pin "2") (pinfunction "2_2") (pintype "input"))
      (node (ref "U1") (pin "2") (pinfunction "3V3_2") (pintype "input"))
    )
    (net (code "51") (name "GND") (class "Default")
      (node (ref "B1") (pin "2") (pinfunction "2_2") (pintype "input"))
      (node (ref "BT1") (pin "2") (pinfunction "2_2") (pintype "input"))
      (node (ref "C1") (pin "1") (pinfunction "1_1") (pintype "input"))
      (node (ref "C10") (pin "1") (pinfunction "1_1") (pintype "input"))
      (node (ref "C11") (pin "1") (pinfunction "1_1") (pintype "input"))
      (node (ref "C12") (pin "2") (pinfunction "2_2") (pintype "input"))
      (node (ref "C2") (pin "1") (pinfunction "1_1") (pintype "input"))
      (node (ref "C3") (pin "1") (pinfunction "1_1") (pintype "input"))
      (node (ref "C4") (pin "1") (pinfunction "1_1") (pintype "input"))
      (node (ref "C5") (pin "1") (pinfunction "1_1") (pintype "input"))
      (node (ref "C6") (pin "1") (pinfunction "1_1") (pintype "input"))
      (node (ref "C7") (pin "1") (pinfunction "1_1") (pintype "input"))
      (node (ref "C8") (pin "1") (pinfunction "1_1") (pintype "input"))
      (node (ref "C9") (pin "1") (pinfunction "1_1") (pintype "input"))
      (node (ref "D2") (pin "1") (pinfunction "1_1") (pintype "input"))
      (node (ref "D3") (pin "1") (pinfunction "1_1") (pintype "input"))
      (node (ref "D4") (pin "1") (pinfunction "1_1") (pintype "input"))
      (node (ref "LED1") (pin "1") (pinfunction "K_1") (pintype "input"))
      (node (ref "Q1") (pin "1") (pinfunction "S_1") (pintype "input"))
      (node (ref "Q1") (pin "4") (pinfunction "S_4") (pintype "input"))
      (node (ref "Q2") (pin "1") (pinfunction "S_1") (pintype "input"))
      (node (ref "R11") (pin "1") (pinfunction "1_1") (pintype "input"))
      (node (ref "R13") (pin "1") (pinfunction "1_1") (pintype "input"))
      (node (ref "R22") (pin "1") (pinfunction "1_1") (pintype "input"))
      (node (ref "R5") (pin "1") (pinfunction "1_1") (pintype "input"))
      (node (ref "SW1") (pin "2") (pinfunction "2_2") (pintype "input"))
      (node (ref "SW2") (pin "2") (pinfunction "2_2") (pintype "input"))
      (node (ref "U1") (pin "1") (pinfunction "GND_1") (pintype "input"))
      (node (ref "U1") (pin "40") (pinfunction "GND_40") (pintype "input"))
      (node (ref "U1") (pin "41") (pinfunction "GND_41") (pintype "input"))
      (node (ref "U12") (pin "2") (pinfunction "2_2") (pintype "input"))
      (node (ref "U2") (pin "2") (pinfunction "GND_2") (pintype "input"))
      (node (ref "U3") (pin "5") (pinfunction "GND_5") (pintype "input"))
      (node (ref "U4") (pin "29") (pinfunction "EP_29") (pintype "input"))
      (node (ref "U4") (pin "3") (pinfunction "GND_3") (pintype "input"))
      (node (ref "U5") (pin "4") (pinfunction "GND_4") (pintype "input"))
      (node (ref "U6") (pin "4") (pinfunction "GND_4") (pintype "input"))
      (node (ref "U7") (pin "11") (pinfunction "V-_11") (pintype "input"))
      (node (ref "U8") (pin "11") (pinfunction "V-_11") (pintype "input"))
      (node (ref "U9") (pin "11") (pinfunction "V-_11") (pintype "input"))
      (node (ref "USB1") (pin "5") (pinfunction "GND_5") (pintype "input"))
      (node (ref "USB1") (pin "6") (pinfunction "SH1_6") (pintype "input"))
      (node (ref "USB1") (pin "7") (pinfunction "SH2_7") (pintype "input"))
      (node (ref "USB1") (pin "8") (pinfunction "SH3_8") (pintype "input"))
      (node (ref "USB1") (pin "9") (pinfunction "SH4_9") (pintype "input"))
    )
    (net (code "52") (name "IRQ#") (class "Default")
      (node (ref "R2") (pin "1") (pinfunction "1_1") (pintype "input"))
      (node (ref "U1") (pin "16") (pinfunction "IO46_16") (pintype "input"))
      (node (ref "U5") (pin "7") (pinfunction "IRQ#_7") (pintype "input"))
    )
    (net (code "53") (name "Net-(LED1-A)") (class "Default")
      (node (ref "LED1") (pin "2") (pinfunction "A_2") (pintype "input"))
      (node (ref "R1") (pin "2") (pinfunction "2_2") (pintype "input"))
    )
    (net (code "54") (name "Net-(LED2-A)") (class "Default")
      (node (ref "LED2") (pin "2") (pinfunction "A_2") (pintype "input"))
      (node (ref "R6") (pin "1") (pinfunction "1_1") (pintype "input"))
    )
    (net (code "55") (name "Net-(LED2-K)") (class "Default")
      (node (ref "LED2") (pin "1") (pinfunction "K_1") (pintype "input"))
      (node (ref "U3") (pin "3") (pinfunction "CHG#_3") (pintype "input"))
    )
    (net (code "56") (name "Net-(Q1-D-Pad3)") (class "Default")
      (node (ref "Q1") (pin "3") (pinfunction "D_3") (pintype "input"))
      (node (ref "Q1") (pin "8") (pinfunction "D_8") (pintype "input"))
      (node (ref "R8") (pin "1") (pinfunction "1_1") (pintype "input"))
    )
    (net (code "57") (name "Net-(Q1-D-Pad6)") (class "Default")
      (node (ref "Q1") (pin "6") (pinfunction "D_6") (pintype "input"))
      (node (ref "Q1") (pin "7") (pinfunction "D_7") (pintype "input"))
      (node (ref "R7") (pin "1") (pinfunction "1_1") (pintype "input"))
    )
    (net (code "58") (name "Net-(Q2-D-Pad6)") (class "Default")
      (node (ref "Q2") (pin "6") (pinfunction "D_6") (pintype "input"))
      (node (ref "Q2") (pin "7") (pinfunction "D_7") (pintype "input"))
      (node (ref "R9") (pin "1") (pinfunction "1_1") (pintype "input"))
    )
    (net (code "59") (name "Net-(Q3-B)") (class "Default")
      (node (ref "Q3") (pin "1") (pinfunction "B_1") (pintype "input"))
      (node (ref "R15") (pin "2") (pinfunction "2_2") (pintype "input"))
    )
    (net (code "60") (name "Net-(Q3-C)") (class "Default")
      (node (ref "Q3") (pin "3") (pinfunction "C_3") (pintype "input"))
      (node (ref "R17") (pin "1") (pinfunction "1_1") (pintype "input"))
    )
    (net (code "61") (name "Net-(Q4-B)") (class "Default")
      (node (ref "Q4") (pin "1") (pinfunction "B_1") (pintype "input"))
      (node (ref "R16") (pin "2") (pinfunction "2_2") (pintype "input"))
    )
    (net (code "62") (name "Net-(Q4-C)") (class "Default")
      (node (ref "Q4") (pin "3") (pinfunction "C_3") (pintype "input"))
      (node (ref "R18") (pin "1") (pinfunction "1_1") (pintype "input"))
    )
    (net (code "63") (name "Net-(U2-EN)") (class "Default")
      (node (ref "SW3") (pin "1") (pinfunction "1_1") (pintype "input"))
      (node (ref "SW3") (pin "2") (pinfunction "2_2") (pintype "input"))
      (node (ref "U2") (pin "1") (pinfunction "IN_1") (pintype "input"))
      (node (ref "U2") (pin "3") (pinfunction "EN_3") (pintype "input"))
    )
    (net (code "64") (name "Net-(U3-ISET)") (class "Default")
      (node (ref "R7") (pin "2") (pinfunction "2_2") (pintype "input"))
      (node (ref "R8") (pin "2") (pinfunction "2_2") (pintype "input"))
      (node (ref "R9") (pin "2") (pinfunction "2_2") (pintype "input"))
      (node (ref "U3") (pin "4") (pinfunction "ISET_4") (pintype "input"))
    )
    (net (code "65") (name "Net-(U3-TS)") (class "Default")
      (node (ref "R5") (pin "2") (pinfunction "2_2") (pintype "input"))
      (node (ref "U3") (pin "1") (pinfunction "TS_1") (pintype "input"))
    )
    (net (code "66") (name "Net-(U4-RSTb)") (class "Default")
      (node (ref "R12") (pin "1") (pinfunction "1_1") (pintype "input"))
      (node (ref "U4") (pin "9") (pinfunction "RSTb_9") (pintype "input"))
    )
    (net (code "67") (name "Net-(U4-SUSPENDb)") (class "Default")
      (node (ref "R13") (pin "2") (pinfunction "2_2") (pintype "input"))
      (node (ref "U4") (pin "11") (pinfunction "SUSPENDb_11") (pintype "input"))
    )
    (net (code "68") (name "Net-(U4-VBUS)") (class "Default")
      (node (ref "C6") (pin "2") (pinfunction "2_2") (pintype "input"))
      (node (ref "R10") (pin "1") (pinfunction "1_1") (pintype "input"))
      (node (ref "R11") (pin "2") (pinfunction "2_2") (pintype "input"))
      (node (ref "U4") (pin "8") (pinfunction "VBUS_8") (pintype "input"))
    )
    (net (code "69") (name "Net-(U5-OSCI)") (class "Default")
      (node (ref "U5") (pin "1") (pinfunction "OSCI_1") (pintype "input"))
      (node (ref "X1") (pin "1") (pinfunction "1_1") (pintype "input"))
    )
    (net (code "70") (name "Net-(U5-OSCO)") (class "Default")
      (node (ref "U5") (pin "2") (pinfunction "OSCO_2") (pintype "input"))
      (node (ref "X1") (pin "2") (pinfunction "GND_2") (pintype "input"))
    )
    (net (code "71") (name "Net-(U5-VBACK)") (class "Default")
      (node (ref "B1") (pin "1") (pinfunction "1_1") (pintype "input"))
      (node (ref "U5") (pin "3") (pinfunction "VBACK_3") (pintype "input"))
    )
    (net (code "72") (name "Net-(U6-DIN)") (class "Default")
      (node (ref "R14") (pin "1") (pinfunction "1_1") (pintype "input"))
      (node (ref "U6") (pin "1") (pinfunction "DIN_1") (pintype "input"))
    )
    (net (code "73") (name "Net-(U7D-IN_A+)") (class "Default")
      (node (ref "R21") (pin "1") (pinfunction "1_1") (pintype "input"))
      (node (ref "R22") (pin "2") (pinfunction "2_2") (pintype "input"))
      (node (ref "U7") (pin "3") (pinfunction "IN_A+_3") (pintype "input"))
    )
    (net (code "74") (name "SCL") (class "Default")
      (node (ref "R3") (pin "1") (pinfunction "1_1") (pintype "input"))
      (node (ref "U1") (pin "24") (pinfunction "IO47_24") (pintype "input"))
      (node (ref "U5") (pin "6") (pinfunction "SCL_6") (pintype "input"))
    )
    (net (code "75") (name "SDA") (class "Default")
      (node (ref "R4") (pin "1") (pinfunction "1_1") (pintype "input"))
      (node (ref "U1") (pin "25") (pinfunction "IO48_25") (pintype "input"))
      (node (ref "U5") (pin "5") (pinfunction "SDA_5") (pintype "input"))
    )
    (net (code "76") (name "U0RXD") (class "Default")
      (node (ref "U1") (pin "36") (pinfunction "RXD0_36") (pintype "input"))
      (node (ref "U12") (pin "12") (pinfunction "12_12") (pintype "input"))
      (node (ref "U4") (pin "26") (pinfunction "TXD_26") (pintype "input"))
    )
    (net (code "77") (name "U0TXD") (class "Default")
      (node (ref "U1") (pin "37") (pinfunction "TXD0_37") (pintype "input"))
      (node (ref "U12") (pin "11") (pinfunction "11_11") (pintype "input"))
      (node (ref "U4") (pin "25") (pinfunction "RXD_25") (pintype "input"))
    )
    (net (code "78") (name "USB_D+") (class "Default")
      (node (ref "D4") (pin "2") (pinfunction "2_2") (pintype "input"))
      (node (ref "U4") (pin "4") (pinfunction "D+_4") (pintype "input"))
      (node (ref "USB1") (pin "3") (pinfunction "D+_3") (pintype "input"))
    )
    (net (code "79") (name "USB_D-") (class "Default")
      (node (ref "D3") (pin "2") (pinfunction "2_2") (pintype "input"))
      (node (ref "U4") (pin "5") (pinfunction "D-_5") (pintype "input"))
      (node (ref "USB1") (pin "2") (pinfunction "D-_2") (pintype "input"))
    )
    (net (code "80") (name "VBAT") (class "Default")
      (node (ref "BT1") (pin "1") (pinfunction "1_1") (pintype "input"))
      (node (ref "C1") (pin "2") (pinfunction "2_2") (pintype "input"))
      (node (ref "R6") (pin "2") (pinfunction "2_2") (pintype "input"))
      (node (ref "SW3") (pin "3") (pinfunction "3_3") (pintype "input"))
      (node (ref "U3") (pin "2") (pinfunction "OUT_2") (pintype "input"))
      (node (ref "U4") (pin "7") (pinfunction "VREGIN_7") (pintype "input"))
    )
    (net (code "81") (name "VBUS") (class "Default")
      (node (ref "D1") (pin "2") (pinfunction "A_2") (pintype "input"))
      (node (ref "D2") (pin "2") (pinfunction "2_2") (pintype "input"))
      (node (ref "R10") (pin "2") (pinfunction "2_2") (pintype "input"))
      (node (ref "U3") (pin "6") (pinfunction "VIN_6") (pintype "input"))
      (node (ref "USB1") (pin "1") (pinfunction "VBUS_1") (pintype "input"))
    )
    (net (code "82") (name "VCC_3V3") (class "Default")
      (node (ref "C12") (pin "1") (pinfunction "1_1") (pintype "input"))
      (node (ref "C2") (pin "2") (pinfunction "2_2") (pintype "input"))
      (node (ref "C3") (pin "2") (pinfunction "2_2") (pintype "input"))
      (node (ref "C5") (pin "2") (pinfunction "2_2") (pintype "input"))
      (node (ref "C7") (pin "2") (pinfunction "2_2") (pintype "input"))
      (node (ref "C8") (pin "2") (pinfunction "2_2") (pintype "input"))
      (node (ref "R1") (pin "1") (pinfunction "1_1") (pintype "input"))
      (node (ref "R12") (pin "2") (pinfunction "2_2") (pintype "input"))
      (node (ref "R19") (pin "1") (pinfunction "1_1") (pintype "input"))
      (node (ref "R2") (pin "2") (pinfunction "2_2") (pintype "input"))
      (node (ref "R21") (pin "2") (pinfunction "2_2") (pintype "input"))
      (node (ref "R3") (pin "2") (pinfunction "2_2") (pintype "input"))
      (node (ref "R4") (pin "2") (pinfunction "2_2") (pintype "input"))
      (node (ref "U12") (pin "1") (pinfunction "1_1") (pintype "input"))
      (node (ref "U2") (pin "5") (pinfunction "OUT_5") (pintype "input"))
      (node (ref "U4") (pin "6") (pinfunction "VDD_6") (pintype "input"))
      (node (ref "U5") (pin "8") (pinfunction "VCC_8") (pintype "input"))
      (node (ref "U6") (pin "2") (pinfunction "VDD_2") (pintype "input"))
      (node (ref "U7") (pin "4") (pinfunction "V+_4") (pintype "input"))
      (node (ref "U8") (pin "4") (pinfunction "V+_4") (pintype "input"))
      (node (ref "U9") (pin "4") (pinfunction "V+_4") (pintype "input"))
    )
    (net (code "83") (name "VCC_5V") (class "Default")
      (node (ref "C4") (pin "2") (pinfunction "2_2") (pintype "input"))
      (node (ref "D1") (pin "1") (pinfunction "K_1") (pintype "input"))
    )
    (net (code "84") (name "unconnected-(Q2-D-Pad3)") (class "Default")
      (node (ref "Q2") (pin "3") (pinfunction "D_3") (pintype "input+no_connect"))
    )
    (net (code "85") (name "unconnected-(Q2-D-Pad8)") (class "Default")
      (node (ref "Q2") (pin "8") (pinfunction "D_8") (pintype "input+no_connect"))
    )
    (net (code "86") (name "unconnected-(Q2-G-Pad5)") (class "Default")
      (node (ref "Q2") (pin "5") (pinfunction "G_5") (pintype "input+no_connect"))
    )
    (net (code "87") (name "unconnected-(Q2-S-Pad4)") (class "Default")
      (node (ref "Q2") (pin "4") (pinfunction "S_4") (pintype "input+no_connect"))
    )
    (net (code "88") (name "unconnected-(SW3-Pad4)") (class "Default")
      (node (ref "SW3") (pin "4") (pinfunction "4_4") (pintype "input+no_connect"))
    )
    (net (code "89") (name "unconnected-(SW3-Pad5)") (class "Default")
      (node (ref "SW3") (pin "5") (pinfunction "5_5") (pintype "input+no_connect"))
    )
    (net (code "90") (name "unconnected-(SW3-Pad6)") (class "Default")
      (node (ref "SW3") (pin "6") (pinfunction "6_6") (pintype "input+no_connect"))
    )
    (net (code "91") (name "unconnected-(U2-NC-Pad4)") (class "Default")
      (node (ref "U2") (pin "4") (pinfunction "NC_4") (pintype "input+no_connect"))
    )
    (net (code "92") (name "unconnected-(U4-CTS-Pad23)") (class "Default")
      (node (ref "U4") (pin "23") (pinfunction "CTS_23") (pintype "input+no_connect"))
    )
    (net (code "93") (name "unconnected-(U4-DCD-Pad1)") (class "Default")
      (node (ref "U4") (pin "1") (pinfunction "DCD_1") (pintype "input+no_connect"))
    )
    (net (code "94") (name "unconnected-(U4-DSR-Pad27)") (class "Default")
      (node (ref "U4") (pin "27") (pinfunction "DSR_27") (pintype "input+no_connect"))
    )
    (net (code "95") (name "unconnected-(U4-GPIO.0{slash}TXT-Pad19)") (class "Default")
      (node (ref "U4") (pin "19") (pinfunction "GPIO.0/TXT_19") (pintype "input+no_connect"))
    )
    (net (code "96") (name "unconnected-(U4-GPIO.1{slash}RXT-Pad18)") (class "Default")
      (node (ref "U4") (pin "18") (pinfunction "GPIO.1/RXT_18") (pintype "input+no_connect"))
    )
    (net (code "97") (name "unconnected-(U4-GPIO.2{slash}RS485-Pad17)") (class "Default")
      (node (ref "U4") (pin "17") (pinfunction "GPIO.2/RS485_17") (pintype "input+no_connect"))
    )
    (net (code "98") (name "unconnected-(U4-GPIO.3{slash}WAKEUP-Pad16)") (class "Default")
      (node (ref "U4") (pin "16") (pinfunction "GPIO.3/WAKEUP_16") (pintype "input+no_connect"))
    )
    (net (code "99") (name "unconnected-(U4-GPIO.4-Pad22)") (class "Default")
      (node (ref "U4") (pin "22") (pinfunction "GPIO.4_22") (pintype "input+no_connect"))
    )
    (net (code "100") (name "unconnected-(U4-GPIO.5-Pad21)") (class "Default")
      (node (ref "U4") (pin "21") (pinfunction "GPIO.5_21") (pintype "input+no_connect"))
    )
    (net (code "101") (name "unconnected-(U4-GPIO.6-Pad20)") (class "Default")
      (node (ref "U4") (pin "20") (pinfunction "GPIO.6_20") (pintype "input+no_connect"))
    )
    (net (code "102") (name "unconnected-(U4-NC-Pad10)") (class "Default")
      (node (ref "U4") (pin "10") (pinfunction "NC_10") (pintype "input+no_connect"))
    )
    (net (code "103") (name "unconnected-(U4-RI{slash}CLK-Pad2)") (class "Default")
      (node (ref "U4") (pin "2") (pinfunction "RI/CLK_2") (pintype "input+no_connect"))
    )
    (net (code "104") (name "unconnected-(U4-SUSPEND-Pad12)") (class "Default")
      (node (ref "U4") (pin "12") (pinfunction "SUSPEND_12") (pintype "input+no_connect"))
    )
    (net (code "105") (name "unconnected-(U6-DOUT-Pad3)") (class "Default")
      (node (ref "U6") (pin "3") (pinfunction "DOUT_3") (pintype "input+no_connect"))
    )
    (net (code "106") (name "unconnected-(USB1-ID-Pad4)") (class "Default")
      (node (ref "USB1") (pin "4") (pinfunction "ID_4") (pintype "input+no_connect"))
    )
  )
)
